# Shore_Power.net
KiCad netlist of a schematic drawn in Altium Designer
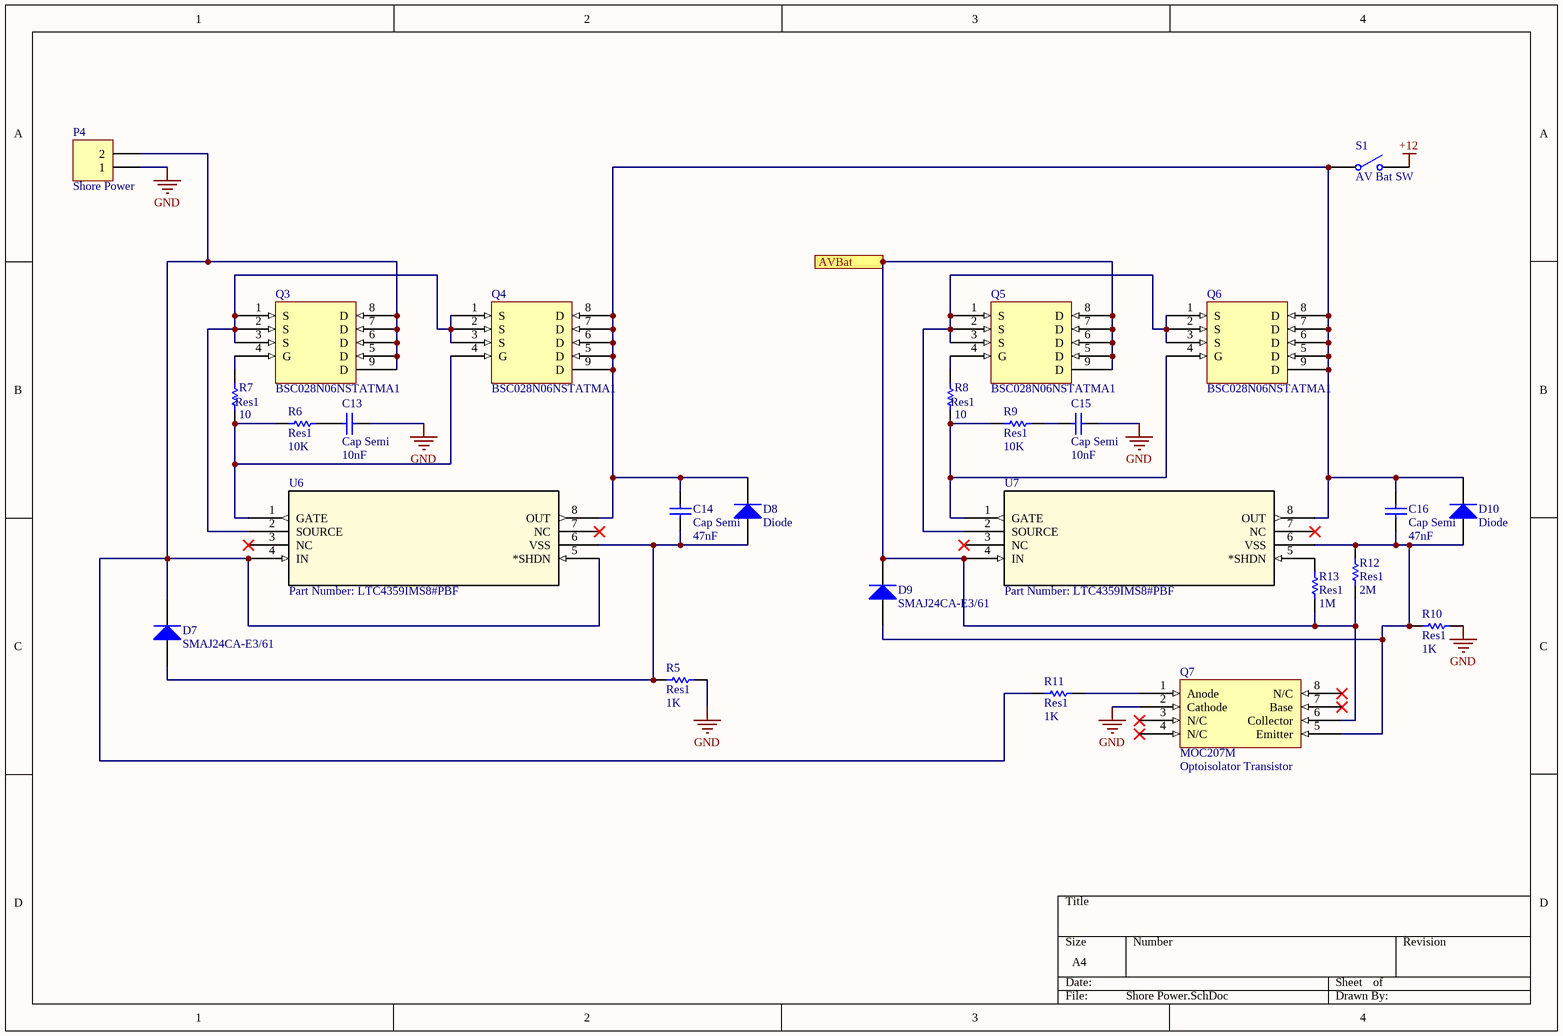
[diagram p0: Shore Power.SchDoc]

(export (version "E")
  (design (tool "Eeschema 10.0.6"))
  (components
    (comp (ref "C13")
      (value "Cap Semi")
      (footprint "C1206")
      (description "Capacitor (Semiconductor SIM Model)")
      (fields (field (name "ALTIUM_VALUE") "10nF") (field (name "PUBLISHER") "Altium Limited"))
      (libsource (lib "Miscellaneous Devices") (part "Cap Semi"))
    )
    (comp (ref "C14")
      (value "Cap Semi")
      (footprint "C1206")
      (description "Capacitor (Semiconductor SIM Model)")
      (fields (field (name "ALTIUM_VALUE") "47nF") (field (name "PUBLISHER") "Altium Limited"))
      (libsource (lib "Miscellaneous Devices") (part "Cap Semi"))
    )
    (comp (ref "C15")
      (value "Cap Semi")
      (footprint "C1206")
      (description "Capacitor (Semiconductor SIM Model)")
      (fields (field (name "ALTIUM_VALUE") "10nF") (field (name "PUBLISHER") "Altium Limited"))
      (libsource (lib "Miscellaneous Devices") (part "Cap Semi"))
    )
    (comp (ref "C16")
      (value "Cap Semi")
      (footprint "C1206")
      (description "Capacitor (Semiconductor SIM Model)")
      (fields (field (name "ALTIUM_VALUE") "47nF") (field (name "PUBLISHER") "Altium Limited"))
      (libsource (lib "Miscellaneous Devices") (part "Cap Semi"))
    )
    (comp (ref "D7")
      (value "SMAJ24CA-E3/61")
      (footprint "DIODE_DO-214AC")
      (description "Default Diode")
      (fields (field (name "PUBLISHER") "Altium Limited"))
      (libsource (lib "Miscellaneous Devices") (part "Diode"))
    )
    (comp (ref "D8")
      (value "Diode")
      (footprint "DIOM4427X27N")
      (description "Default Diode")
      (fields (field (name "PUBLISHER") "Altium Limited"))
      (libsource (lib "Miscellaneous Devices") (part "Diode"))
    )
    (comp (ref "D9")
      (value "SMAJ24CA-E3/61")
      (footprint "DIODE_DO-214AC")
      (description "Default Diode")
      (fields (field (name "PUBLISHER") "Altium Limited"))
      (libsource (lib "Miscellaneous Devices") (part "Diode"))
    )
    (comp (ref "D10")
      (value "Diode")
      (footprint "DIOM4427X27N")
      (description "Default Diode")
      (fields (field (name "PUBLISHER") "Altium Limited"))
      (libsource (lib "Miscellaneous Devices") (part "Diode"))
    )
    (comp (ref "P4")
      (value "Shore Power")
      (footprint "M80-5000000M5-02-333-00-000")
      (description "Header, 2-Pin")
      (fields (field (name "PUBLISHER") "Altium Limited"))
      (libsource (lib "Miscellaneous Connectors") (part "Header 2"))
    )
    (comp (ref "Q3")
      (value "BSC028N06NSTATMA1")
      (footprint "FDMS86101A")
      (description "MOSFET N-CH 100V 13A POWER56")
      (libsource (lib "FDMS86101A") (part "FDMS86101A"))
    )
    (comp (ref "Q4")
      (value "BSC028N06NSTATMA1")
      (footprint "FDMS86101A")
      (description "MOSFET N-CH 100V 13A POWER56")
      (libsource (lib "FDMS86101A") (part "FDMS86101A"))
    )
    (comp (ref "Q5")
      (value "BSC028N06NSTATMA1")
      (footprint "FDMS86101A")
      (description "MOSFET N-CH 100V 13A POWER56")
      (libsource (lib "FDMS86101A") (part "FDMS86101A"))
    )
    (comp (ref "Q6")
      (value "BSC028N06NSTATMA1")
      (footprint "FDMS86101A")
      (description "MOSFET N-CH 100V 13A POWER56")
      (libsource (lib "FDMS86101A") (part "FDMS86101A"))
    )
    (comp (ref "Q7")
      (value "MOC207M")
      (footprint "SOIC127P590X363-8N")
      (description "Optoisolator Transistor")
      (fields (field (name "DESC") "Optoisolator Transistor"))
      (libsource (lib "MOC207M") (part "MOC207M"))
    )
    (comp (ref "R5")
      (value "Res1")
      (footprint "STA_RMCF2512")
      (description "Resistor")
      (fields (field (name "ALTIUM_VALUE") "1K") (field (name "PUBLISHER") "Altium Limited"))
      (libsource (lib "Miscellaneous Devices") (part "Res1"))
    )
    (comp (ref "R6")
      (value "Res1")
      (footprint "6-0805_L")
      (description "Resistor")
      (fields (field (name "ALTIUM_VALUE") "10K") (field (name "PUBLISHER") "Altium Limited"))
      (libsource (lib "Miscellaneous Devices") (part "Res1"))
    )
    (comp (ref "R7")
      (value "Res1")
      (footprint "6-0805_L")
      (description "Resistor")
      (fields (field (name "ALTIUM_VALUE") "10") (field (name "PUBLISHER") "Altium Limited"))
      (libsource (lib "Miscellaneous Devices") (part "Res1"))
    )
    (comp (ref "R8")
      (value "Res1")
      (footprint "6-0805_L")
      (description "Resistor")
      (fields (field (name "ALTIUM_VALUE") "10") (field (name "PUBLISHER") "Altium Limited"))
      (libsource (lib "Miscellaneous Devices") (part "Res1"))
    )
    (comp (ref "R9")
      (value "Res1")
      (footprint "6-0805_L")
      (description "Resistor")
      (fields (field (name "ALTIUM_VALUE") "10K") (field (name "PUBLISHER") "Altium Limited"))
      (libsource (lib "Miscellaneous Devices") (part "Res1"))
    )
    (comp (ref "R10")
      (value "Res1")
      (footprint "STA_RMCF2512")
      (description "Resistor")
      (fields (field (name "ALTIUM_VALUE") "1K") (field (name "PUBLISHER") "Altium Limited"))
      (libsource (lib "Miscellaneous Devices") (part "Res1"))
    )
    (comp (ref "R11")
      (value "Res1")
      (footprint "STA_RMCF2512")
      (description "Resistor")
      (fields (field (name "ALTIUM_VALUE") "1K") (field (name "PUBLISHER") "Altium Limited"))
      (libsource (lib "Miscellaneous Devices") (part "Res1"))
    )
    (comp (ref "R12")
      (value "Res1")
      (footprint "J1-0603")
      (description "Resistor")
      (fields (field (name "ALTIUM_VALUE") "2M") (field (name "PUBLISHER") "Altium Limited"))
      (libsource (lib "Miscellaneous Devices") (part "Res1"))
    )
    (comp (ref "R13")
      (value "Res1")
      (footprint "J1-0603")
      (description "Resistor")
      (fields (field (name "ALTIUM_VALUE") "1M") (field (name "PUBLISHER") "Altium Limited"))
      (libsource (lib "Miscellaneous Devices") (part "Res1"))
    )
    (comp (ref "S1")
      (value "AV Bat SW")
      (footprint "M80-5000000M5-02-333-00-000")
      (description "Single-Pole, Single-Throw Switch")
      (fields (field (name "PUBLISHER") "Altium Limited"))
      (libsource (lib "Miscellaneous Devices") (part "SW-SPST"))
    )
    (comp (ref "U6")
      (value "Part Number: LTC4359IMS8#PBF")
      (footprint "MSOP-8_MS")
      (description "No Description Available")
      (fields
        (field (name "MANUFACTURER_PART_NUMBER") "LTC4359IMS8#PBF")
        (field (name "COPYRIGHT") "Copyright (C) 2018 Accelerated Designs. All rights reserved")
      )
      (libsource (lib "LTC4359IMS8#PBF") (part "LTC4359IMS8#PBF"))
    )
    (comp (ref "U7")
      (value "Part Number: LTC4359IMS8#PBF")
      (footprint "MSOP-8_MS")
      (description "No Description Available")
      (fields
        (field (name "MANUFACTURER_PART_NUMBER") "LTC4359IMS8#PBF")
        (field (name "COPYRIGHT") "Copyright (C) 2018 Accelerated Designs. All rights reserved")
      )
      (libsource (lib "LTC4359IMS8#PBF") (part "LTC4359IMS8#PBF"))
    )
  )
  (nets
    (net (code "1") (name "+12") (class "Default")
      (node (ref "S1") (pin "2") (pinfunction "NO_2") (pintype "passive"))
    )
    (net (code "2") (name "/AVBat") (class "Default")
      (node (ref "D9") (pin "2") (pinfunction "K_2") (pintype "passive"))
      (node (ref "Q5") (pin "5") (pinfunction "D_5") (pintype "input"))
      (node (ref "Q5") (pin "6") (pinfunction "D_6") (pintype "input"))
      (node (ref "Q5") (pin "7") (pinfunction "D_7") (pintype "input"))
      (node (ref "Q5") (pin "8") (pinfunction "D_8") (pintype "input"))
      (node (ref "Q5") (pin "9") (pinfunction "D_9") (pintype "passive"))
      (node (ref "Q7") (pin "6") (pinfunction "Collector_6") (pintype "input"))
      (node (ref "R12") (pin "1") (pinfunction "1_1") (pintype "passive"))
      (node (ref "R13") (pin "2") (pinfunction "2_2") (pintype "passive"))
      (node (ref "U7") (pin "4") (pinfunction "IN_4") (pintype "input"))
    )
    (net (code "3") (name "GND") (class "Default")
      (node (ref "C13") (pin "1") (pinfunction "1_1") (pintype "passive"))
      (node (ref "C15") (pin "1") (pinfunction "1_1") (pintype "passive"))
      (node (ref "P4") (pin "1") (pinfunction "1_1") (pintype "passive"))
      (node (ref "Q7") (pin "2") (pinfunction "Cathode_2") (pintype "input"))
      (node (ref "R10") (pin "1") (pinfunction "1_1") (pintype "passive"))
      (node (ref "R5") (pin "1") (pinfunction "1_1") (pintype "passive"))
    )
    (net (code "4") (name "Net-(C13-Pad2)") (class "Default")
      (node (ref "C13") (pin "2") (pinfunction "2_2") (pintype "passive"))
      (node (ref "R6") (pin "2") (pinfunction "2_2") (pintype "passive"))
    )
    (net (code "5") (name "Net-(C15-Pad2)") (class "Default")
      (node (ref "C15") (pin "2") (pinfunction "2_2") (pintype "passive"))
      (node (ref "R9") (pin "2") (pinfunction "2_2") (pintype "passive"))
    )
    (net (code "6") (name "Net-(D7-A)") (class "Default")
      (node (ref "C14") (pin "2") (pinfunction "2_2") (pintype "passive"))
      (node (ref "D7") (pin "1") (pinfunction "A_1") (pintype "passive"))
      (node (ref "D8") (pin "1") (pinfunction "A_1") (pintype "passive"))
      (node (ref "R5") (pin "2") (pinfunction "2_2") (pintype "passive"))
      (node (ref "U6") (pin "6") (pinfunction "VSS_6") (pintype "power_in"))
    )
    (net (code "7") (name "Net-(D7-K)") (class "Default")
      (node (ref "D7") (pin "2") (pinfunction "K_2") (pintype "passive"))
      (node (ref "P4") (pin "2") (pinfunction "2_2") (pintype "passive"))
      (node (ref "Q3") (pin "5") (pinfunction "D_5") (pintype "input"))
      (node (ref "Q3") (pin "6") (pinfunction "D_6") (pintype "input"))
      (node (ref "Q3") (pin "7") (pinfunction "D_7") (pintype "input"))
      (node (ref "Q3") (pin "8") (pinfunction "D_8") (pintype "input"))
      (node (ref "Q3") (pin "9") (pinfunction "D_9") (pintype "passive"))
      (node (ref "R11") (pin "2") (pinfunction "2_2") (pintype "passive"))
      (node (ref "U6") (pin "4") (pinfunction "IN_4") (pintype "input"))
      (node (ref "U6") (pin "5") (pinfunction "*SHDN_5") (pintype "input"))
    )
    (net (code "8") (name "Net-(D10-A)") (class "Default")
      (node (ref "C16") (pin "2") (pinfunction "2_2") (pintype "passive"))
      (node (ref "D10") (pin "1") (pinfunction "A_1") (pintype "passive"))
      (node (ref "D9") (pin "1") (pinfunction "A_1") (pintype "passive"))
      (node (ref "Q7") (pin "5") (pinfunction "Emitter_5") (pintype "input"))
      (node (ref "R10") (pin "2") (pinfunction "2_2") (pintype "passive"))
      (node (ref "R12") (pin "2") (pinfunction "2_2") (pintype "passive"))
      (node (ref "U7") (pin "6") (pinfunction "VSS_6") (pintype "power_in"))
    )
    (net (code "9") (name "Net-(D10-K)") (class "Default")
      (node (ref "C14") (pin "1") (pinfunction "1_1") (pintype "passive"))
      (node (ref "C16") (pin "1") (pinfunction "1_1") (pintype "passive"))
      (node (ref "D10") (pin "2") (pinfunction "K_2") (pintype "passive"))
      (node (ref "D8") (pin "2") (pinfunction "K_2") (pintype "passive"))
      (node (ref "Q4") (pin "5") (pinfunction "D_5") (pintype "input"))
      (node (ref "Q4") (pin "6") (pinfunction "D_6") (pintype "input"))
      (node (ref "Q4") (pin "7") (pinfunction "D_7") (pintype "input"))
      (node (ref "Q4") (pin "8") (pinfunction "D_8") (pintype "input"))
      (node (ref "Q4") (pin "9") (pinfunction "D_9") (pintype "passive"))
      (node (ref "Q6") (pin "5") (pinfunction "D_5") (pintype "input"))
      (node (ref "Q6") (pin "6") (pinfunction "D_6") (pintype "input"))
      (node (ref "Q6") (pin "7") (pinfunction "D_7") (pintype "input"))
      (node (ref "Q6") (pin "8") (pinfunction "D_8") (pintype "input"))
      (node (ref "Q6") (pin "9") (pinfunction "D_9") (pintype "passive"))
      (node (ref "S1") (pin "1") (pinfunction "COMMON_1") (pintype "passive"))
      (node (ref "U6") (pin "8") (pinfunction "OUT_8") (pintype "output"))
      (node (ref "U7") (pin "8") (pinfunction "OUT_8") (pintype "output"))
    )
    (net (code "10") (name "Net-(Q3-G)") (class "Default")
      (node (ref "Q3") (pin "4") (pinfunction "G_4") (pintype "input"))
      (node (ref "R7") (pin "2") (pinfunction "2_2") (pintype "passive"))
    )
    (net (code "11") (name "Net-(Q4-G)") (class "Default")
      (node (ref "Q4") (pin "4") (pinfunction "G_4") (pintype "input"))
      (node (ref "R6") (pin "1") (pinfunction "1_1") (pintype "passive"))
      (node (ref "R7") (pin "1") (pinfunction "1_1") (pintype "passive"))
      (node (ref "U6") (pin "1") (pinfunction "GATE_1") (pintype "output"))
    )
    (net (code "12") (name "Net-(Q5-G)") (class "Default")
      (node (ref "Q5") (pin "4") (pinfunction "G_4") (pintype "input"))
      (node (ref "R8") (pin "2") (pinfunction "2_2") (pintype "passive"))
    )
    (net (code "13") (name "Net-(Q6-G)") (class "Default")
      (node (ref "Q6") (pin "4") (pinfunction "G_4") (pintype "input"))
      (node (ref "R8") (pin "1") (pinfunction "1_1") (pintype "passive"))
      (node (ref "R9") (pin "1") (pinfunction "1_1") (pintype "passive"))
      (node (ref "U7") (pin "1") (pinfunction "GATE_1") (pintype "output"))
    )
    (net (code "14") (name "Net-(Q7-Anode)") (class "Default")
      (node (ref "Q7") (pin "1") (pinfunction "Anode_1") (pintype "input"))
      (node (ref "R11") (pin "1") (pinfunction "1_1") (pintype "passive"))
    )
    (net (code "15") (name "Net-(U6-SOURCE)") (class "Default")
      (node (ref "Q3") (pin "1") (pinfunction "S_1") (pintype "input"))
      (node (ref "Q3") (pin "2") (pinfunction "S_2") (pintype "input"))
      (node (ref "Q3") (pin "3") (pinfunction "S_3") (pintype "input"))
      (node (ref "Q4") (pin "1") (pinfunction "S_1") (pintype "input"))
      (node (ref "Q4") (pin "2") (pinfunction "S_2") (pintype "input"))
      (node (ref "Q4") (pin "3") (pinfunction "S_3") (pintype "input"))
      (node (ref "U6") (pin "2") (pinfunction "SOURCE_2") (pintype "passive"))
    )
    (net (code "16") (name "Net-(U7-*SHDN)") (class "Default")
      (node (ref "R13") (pin "1") (pinfunction "1_1") (pintype "passive"))
      (node (ref "U7") (pin "5") (pinfunction "*SHDN_5") (pintype "input"))
    )
    (net (code "17") (name "Net-(U7-SOURCE)") (class "Default")
      (node (ref "Q5") (pin "1") (pinfunction "S_1") (pintype "input"))
      (node (ref "Q5") (pin "2") (pinfunction "S_2") (pintype "input"))
      (node (ref "Q5") (pin "3") (pinfunction "S_3") (pintype "input"))
      (node (ref "Q6") (pin "1") (pinfunction "S_1") (pintype "input"))
      (node (ref "Q6") (pin "2") (pinfunction "S_2") (pintype "input"))
      (node (ref "Q6") (pin "3") (pinfunction "S_3") (pintype "input"))
      (node (ref "U7") (pin "2") (pinfunction "SOURCE_2") (pintype "passive"))
    )
    (net (code "18") (name "unconnected-(Q7-Base-Pad7)") (class "Default")
      (node (ref "Q7") (pin "7") (pinfunction "Base_7") (pintype "input+no_connect"))
    )
    (net (code "19") (name "unconnected-(Q7-N{slash}C-Pad3)") (class "Default")
      (node (ref "Q7") (pin "3") (pinfunction "N/C_3") (pintype "input+no_connect"))
    )
    (net (code "20") (name "unconnected-(Q7-N{slash}C-Pad4)") (class "Default")
      (node (ref "Q7") (pin "4") (pinfunction "N/C_4") (pintype "input+no_connect"))
    )
    (net (code "21") (name "unconnected-(Q7-N{slash}C-Pad8)") (class "Default")
      (node (ref "Q7") (pin "8") (pinfunction "N/C_8") (pintype "input+no_connect"))
    )
    (net (code "22") (name "unconnected-(U6-NC-Pad3)") (class "Default")
      (node (ref "U6") (pin "3") (pinfunction "NC_3") (pintype "passive+no_connect"))
    )
    (net (code "23") (name "unconnected-(U6-NC-Pad7)") (class "Default")
      (node (ref "U6") (pin "7") (pinfunction "NC_7") (pintype "passive+no_connect"))
    )
    (net (code "24") (name "unconnected-(U7-NC-Pad3)") (class "Default")
      (node (ref "U7") (pin "3") (pinfunction "NC_3") (pintype "passive+no_connect"))
    )
    (net (code "25") (name "unconnected-(U7-NC-Pad7)") (class "Default")
      (node (ref "U7") (pin "7") (pinfunction "NC_7") (pintype "passive+no_connect"))
    )
  )
)
